# SCART_SWITCH-5CH.net
KiCad netlist of a schematic drawn in EAGLE
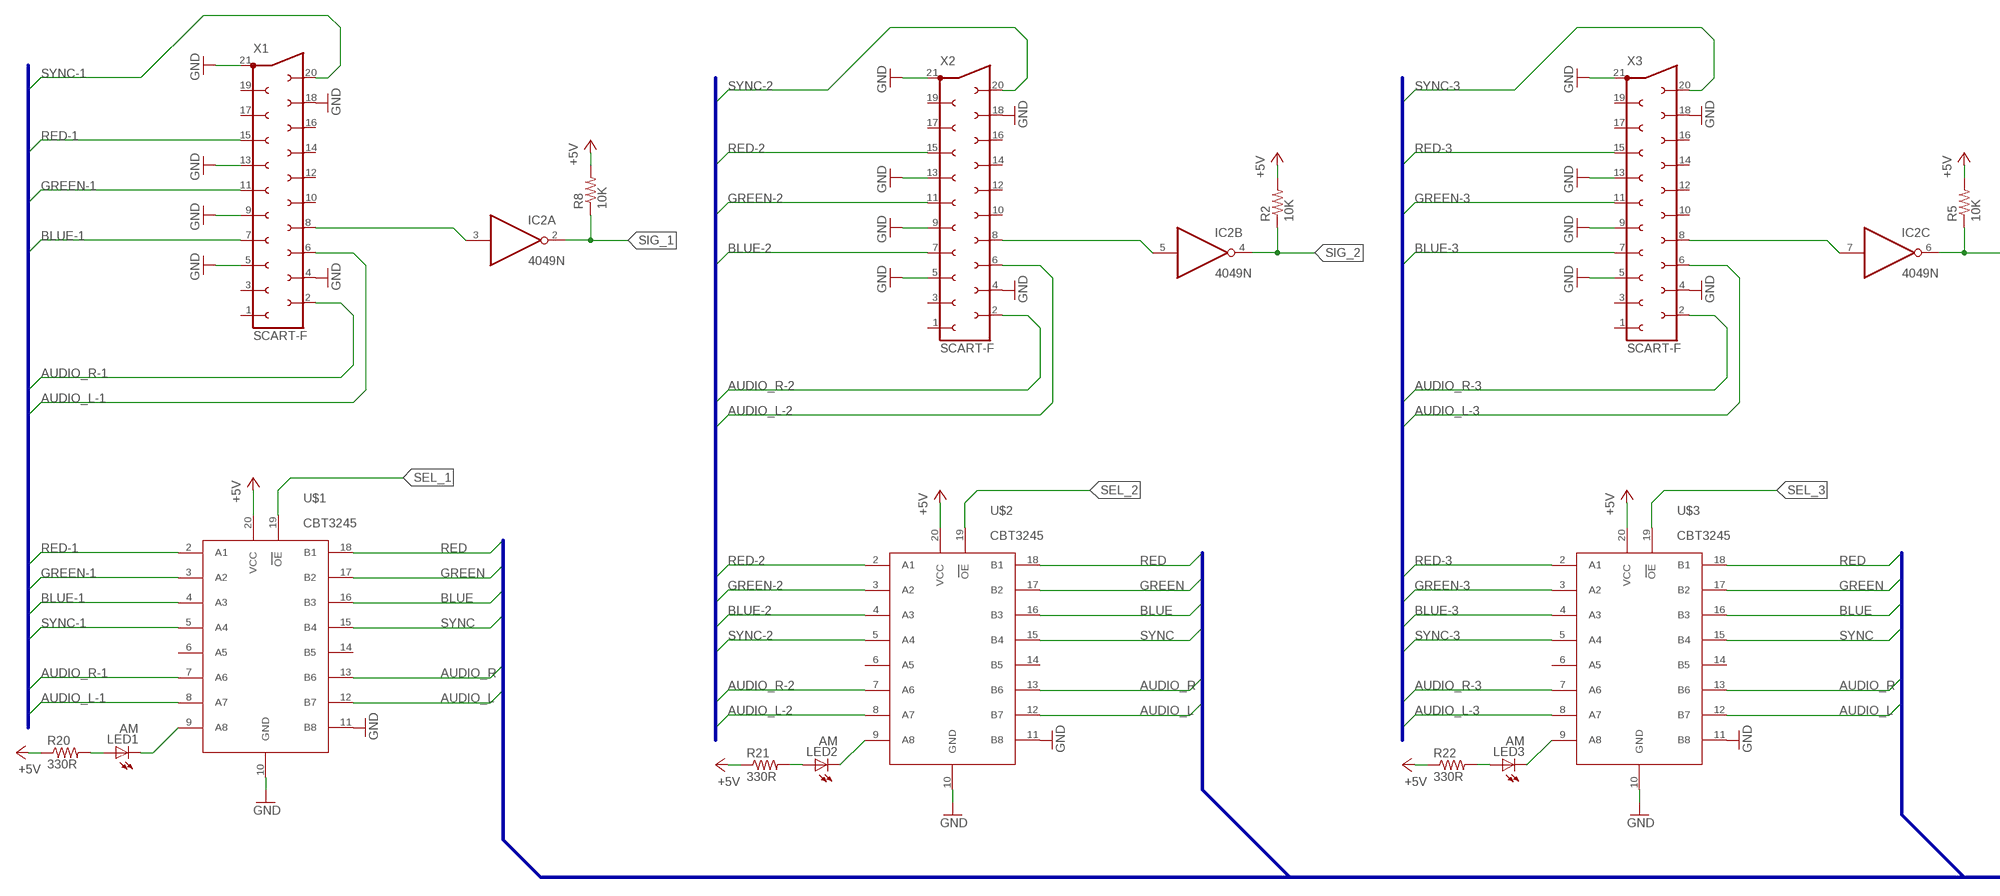
[diagram p0: schematic, sheet 1, part 1 of 2]
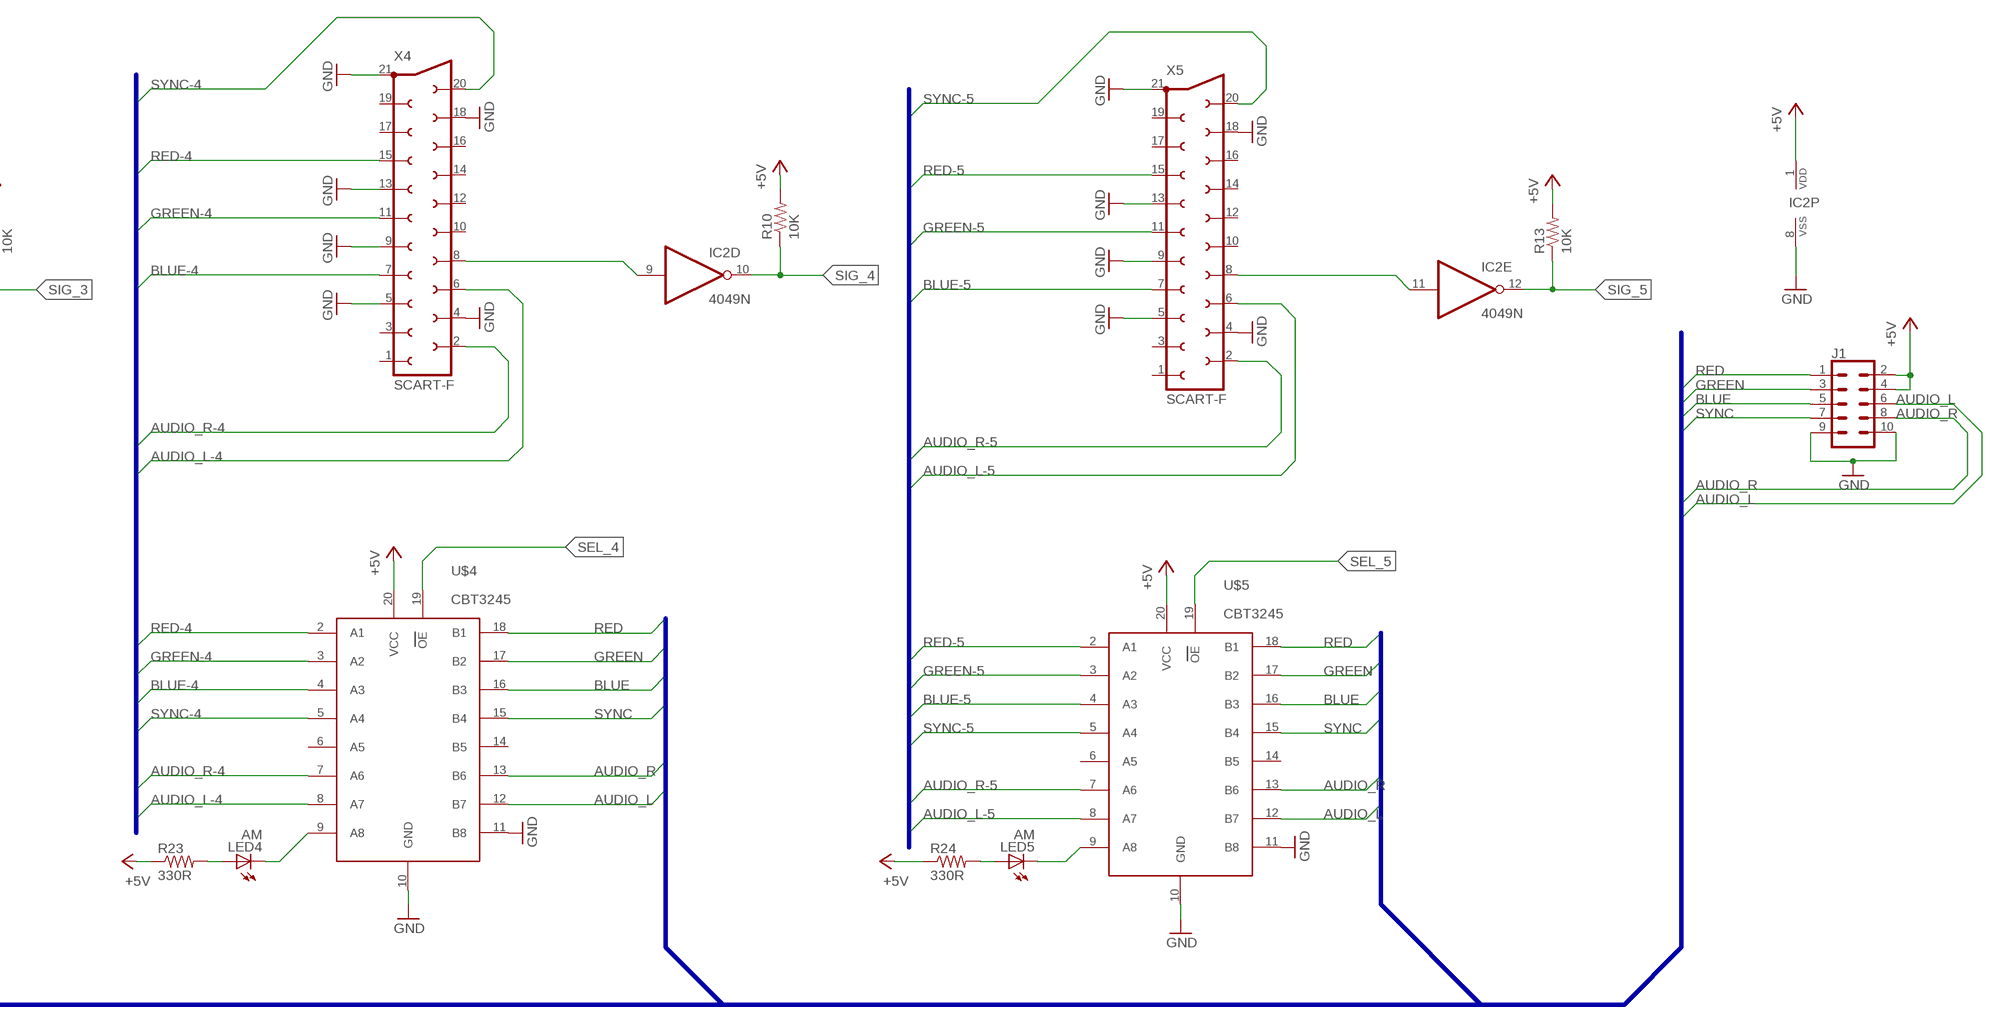
[diagram p1: schematic, sheet 1, part 2 of 2]
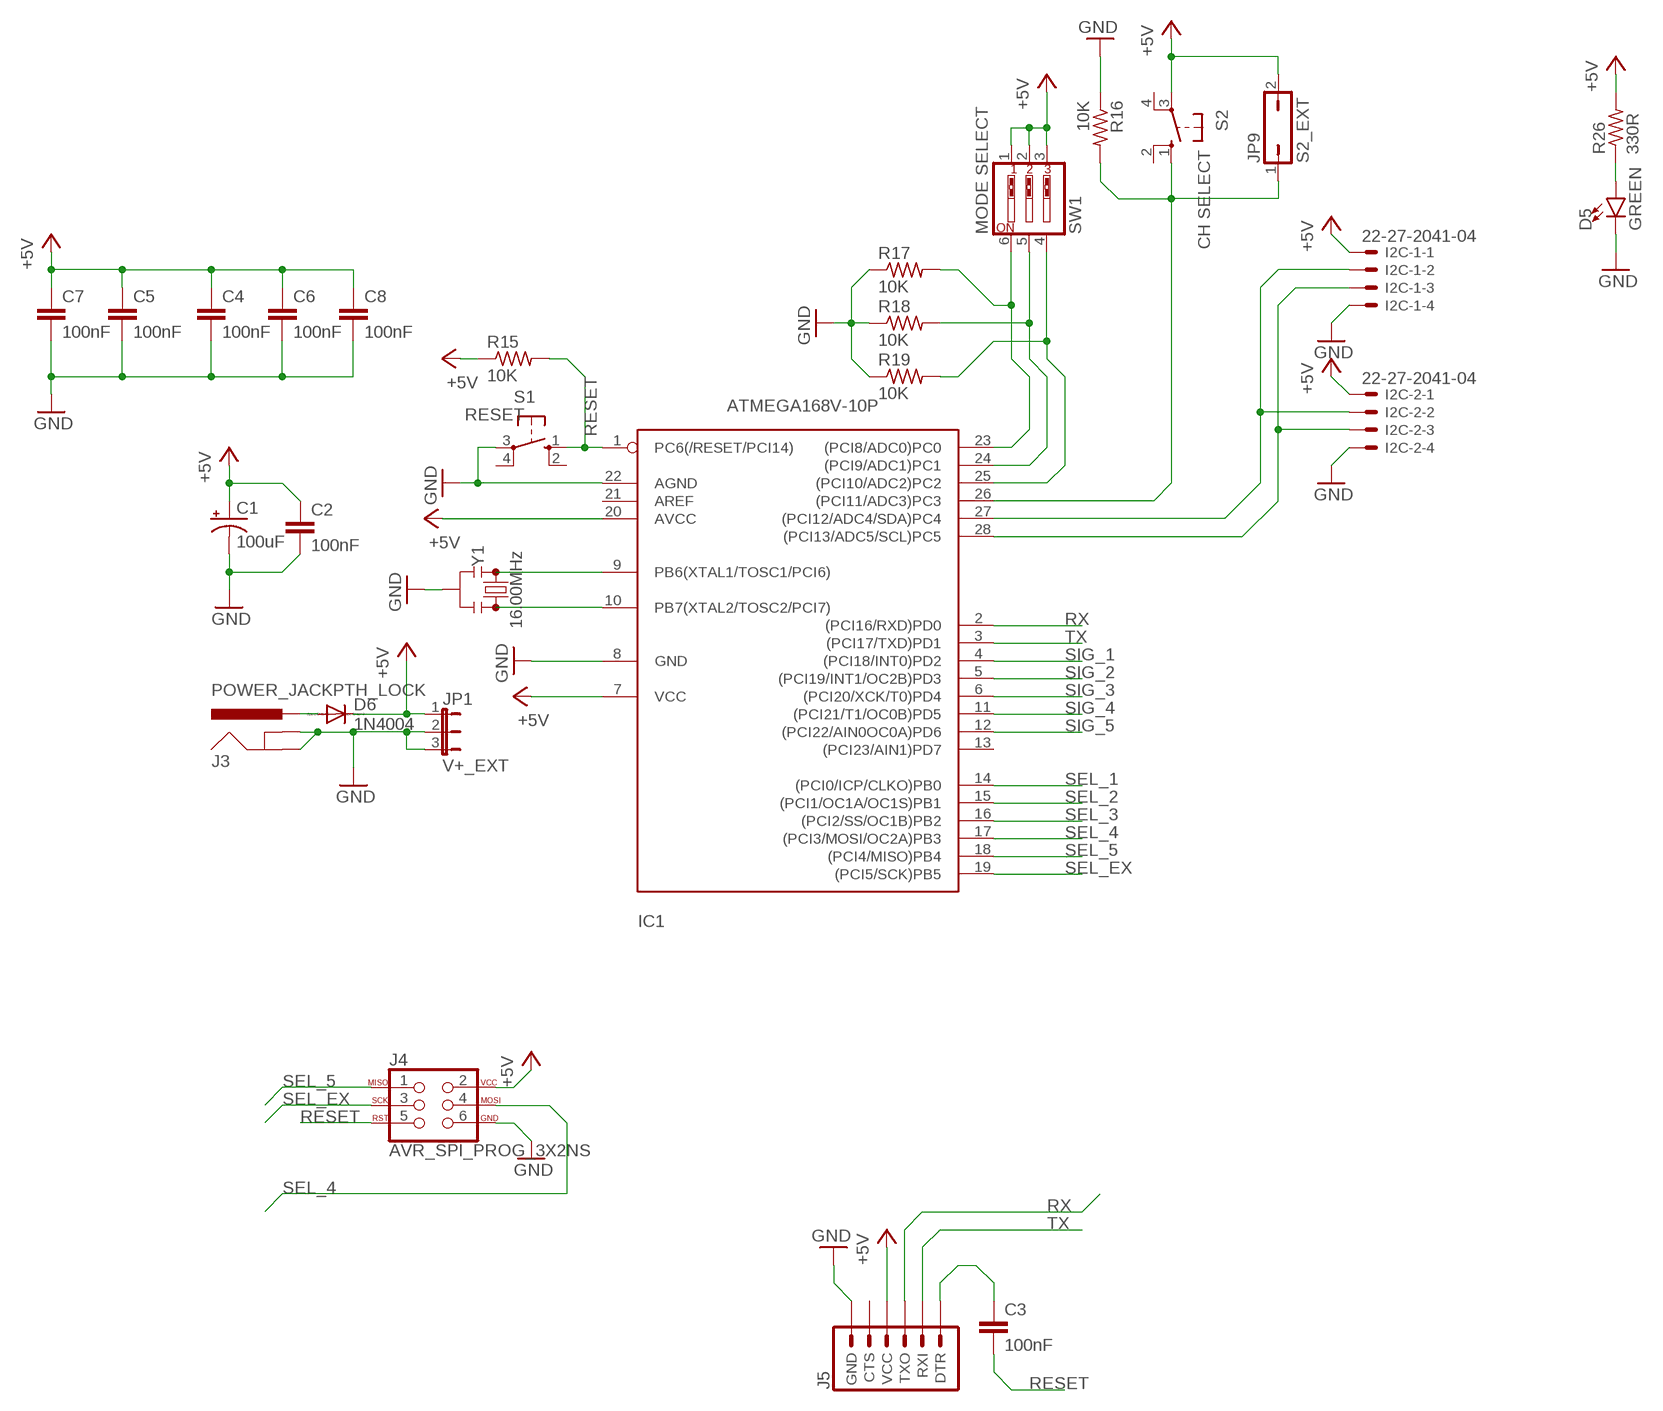
[diagram p2: schematic, sheet 2]

(export (version "E")
  (design (tool "Eeschema 10.0.6"))
  (components
    (comp (ref "IC2")
      (value "4049N")
      (footprint "eagle-import:DIL16")
      (libsource (lib "eagle-import") (part "4049N"))
    )
    (comp (ref "J1")
      (value "CONN_05X2SHD")
      (footprint "eagle-import:2X5-SHROUDED")
      (libsource (lib "eagle-import") (part "CONN_05X2SHD"))
    )
    (comp (ref "LED1")
      (value "AM")
      (footprint "eagle-import:LED5MM")
      (libsource (lib "eagle-import") (part "led_LED5MM"))
    )
    (comp (ref "LED2")
      (value "AM")
      (footprint "eagle-import:LED5MM")
      (libsource (lib "eagle-import") (part "led_LED5MM"))
    )
    (comp (ref "LED3")
      (value "AM")
      (footprint "eagle-import:LED5MM")
      (libsource (lib "eagle-import") (part "led_LED5MM"))
    )
    (comp (ref "LED4")
      (value "AM")
      (footprint "eagle-import:LED5MM")
      (libsource (lib "eagle-import") (part "led_LED5MM"))
    )
    (comp (ref "LED5")
      (value "AM")
      (footprint "eagle-import:LED5MM")
      (libsource (lib "eagle-import") (part "led_LED5MM"))
    )
    (comp (ref "R2")
      (value "10K")
      (footprint "eagle-import:0204_7")
      (libsource (lib "eagle-import") (part "resistor_R-US_0204/7"))
    )
    (comp (ref "R5")
      (value "10K")
      (footprint "eagle-import:0204_7")
      (libsource (lib "eagle-import") (part "resistor_R-US_0204/7"))
    )
    (comp (ref "R8")
      (value "10K")
      (footprint "eagle-import:0204_7")
      (libsource (lib "eagle-import") (part "resistor_R-US_0204/7"))
    )
    (comp (ref "R10")
      (value "10K")
      (footprint "eagle-import:0204_7")
      (libsource (lib "eagle-import") (part "resistor_R-US_0204/7"))
    )
    (comp (ref "R13")
      (value "10K")
      (footprint "eagle-import:0204_7")
      (libsource (lib "eagle-import") (part "resistor_R-US_0204/7"))
    )
    (comp (ref "R20")
      (value "330R")
      (footprint "eagle-import:0207_2V")
      (libsource (lib "eagle-import") (part "R-US_0207/2V"))
    )
    (comp (ref "R21")
      (value "330R")
      (footprint "eagle-import:0207_2V")
      (libsource (lib "eagle-import") (part "R-US_0207/2V"))
    )
    (comp (ref "R22")
      (value "330R")
      (footprint "eagle-import:0207_2V")
      (libsource (lib "eagle-import") (part "R-US_0207/2V"))
    )
    (comp (ref "R23")
      (value "330R")
      (footprint "eagle-import:0207_2V")
      (libsource (lib "eagle-import") (part "R-US_0207/2V"))
    )
    (comp (ref "R24")
      (value "330R")
      (footprint "eagle-import:0207_2V")
      (libsource (lib "eagle-import") (part "R-US_0207/2V"))
    )
    (comp (ref "U$1")
      (value "CBT3245")
      (footprint "eagle-import:SO20")
      (libsource (lib "eagle-import") (part "CBT3245"))
    )
    (comp (ref "U$2")
      (value "CBT3245")
      (footprint "eagle-import:SO20")
      (libsource (lib "eagle-import") (part "CBT3245"))
    )
    (comp (ref "U$3")
      (value "CBT3245")
      (footprint "eagle-import:SO20")
      (libsource (lib "eagle-import") (part "CBT3245"))
    )
    (comp (ref "U$4")
      (value "CBT3245")
      (footprint "eagle-import:SO20")
      (libsource (lib "eagle-import") (part "CBT3245"))
    )
    (comp (ref "U$5")
      (value "CBT3245")
      (footprint "eagle-import:SO20")
      (libsource (lib "eagle-import") (part "CBT3245"))
    )
    (comp (ref "X1")
      (value "SCART-F")
      (footprint "eagle-import:SCART-F")
      (libsource (lib "eagle-import") (part "SCART-F"))
    )
    (comp (ref "X2")
      (value "SCART-F")
      (footprint "eagle-import:SCART-F")
      (libsource (lib "eagle-import") (part "SCART-F"))
    )
    (comp (ref "X3")
      (value "SCART-F")
      (footprint "eagle-import:SCART-F")
      (libsource (lib "eagle-import") (part "SCART-F"))
    )
    (comp (ref "X4")
      (value "SCART-F")
      (footprint "eagle-import:SCART-F")
      (libsource (lib "eagle-import") (part "SCART-F"))
    )
    (comp (ref "X5")
      (value "SCART-F")
      (footprint "eagle-import:SCART-F")
      (libsource (lib "eagle-import") (part "SCART-F"))
    )
    (comp (ref "C1")
      (value "100uF")
      (footprint "eagle-import:E2,5-7")
      (libsource (lib "eagle-import") (part "CPOL-USE2.5-7"))
    )
    (comp (ref "C2")
      (value "100nF")
      (footprint "eagle-import:C075-032X103")
      (libsource (lib "eagle-import") (part "C-EU075-032X103"))
    )
    (comp (ref "C3")
      (value "100nF")
      (footprint "eagle-import:C075-032X103")
      (libsource (lib "eagle-import") (part "C-EU075-032X103"))
    )
    (comp (ref "C4")
      (value "100nF")
      (footprint "eagle-import:C075-032X103")
      (libsource (lib "eagle-import") (part "C-EU075-032X103"))
    )
    (comp (ref "C5")
      (value "100nF")
      (footprint "eagle-import:C075-032X103")
      (libsource (lib "eagle-import") (part "C-EU075-032X103"))
    )
    (comp (ref "C6")
      (value "100nF")
      (footprint "eagle-import:C075-032X103")
      (libsource (lib "eagle-import") (part "C-EU075-032X103"))
    )
    (comp (ref "C7")
      (value "100nF")
      (footprint "eagle-import:C075-032X103")
      (libsource (lib "eagle-import") (part "C-EU075-032X103"))
    )
    (comp (ref "C8")
      (value "100nF")
      (footprint "eagle-import:C075-032X103")
      (libsource (lib "eagle-import") (part "C-EU075-032X103"))
    )
    (comp (ref "D5")
      (value "GREEN")
      (footprint "eagle-import:LED_5MM")
      (libsource (lib "eagle-import") (part "LED5MM"))
    )
    (comp (ref "D6")
      (value "1N4004")
      (footprint "eagle-import:DO41-10")
      (libsource (lib "eagle-import") (part "1N4004"))
    )
    (comp (ref "I2C-1")
      (value "22-27-2041-04")
      (footprint "eagle-import:6410-04")
      (libsource (lib "eagle-import") (part "22-?-0427-2041"))
    )
    (comp (ref "I2C-2")
      (value "22-27-2041-04")
      (footprint "eagle-import:6410-04")
      (libsource (lib "eagle-import") (part "22-?-0427-2041"))
    )
    (comp (ref "IC1")
      (value "ATMEGA168V-10P")
      (footprint "eagle-import:DIL28-3")
      (libsource (lib "eagle-import") (part "ATMEGA168PV-10"))
    )
    (comp (ref "J3")
      (value "POWER_JACKPTH_LOCK")
      (footprint "eagle-import:POWER_JACK_PTH_LOCK")
      (libsource (lib "eagle-import") (part "POWER_JACKPTH_LOCK"))
    )
    (comp (ref "J4")
      (value "AVR_SPI_PROG_3X2NS")
      (footprint "eagle-import:2X3-NS")
      (libsource (lib "eagle-import") (part "AVR_SPI_PROG_3X2NS"))
    )
    (comp (ref "J5")
      (value "6_PIN_SERIAL_TARGETSILK")
      (footprint "eagle-import:6_PIN_SERIAL_TARGET_SIDE_W_SILK")
      (libsource (lib "eagle-import") (part "6_PIN_SERIAL_TARGETSILK"))
    )
    (comp (ref "JP1")
      (value "V+_EXT")
      (footprint "eagle-import:JP2")
      (libsource (lib "eagle-import") (part "JP2E"))
    )
    (comp (ref "JP9")
      (value "S2_EXT")
      (footprint "eagle-import:JP1")
      (libsource (lib "eagle-import") (part "JP1Q"))
    )
    (comp (ref "R15")
      (value "10K")
      (footprint "eagle-import:0204_7")
      (libsource (lib "eagle-import") (part "R-US_0204/7"))
    )
    (comp (ref "R16")
      (value "10K")
      (footprint "eagle-import:0204_7")
      (libsource (lib "eagle-import") (part "R-US_0204/7"))
    )
    (comp (ref "R17")
      (value "10K")
      (footprint "eagle-import:0204_7")
      (libsource (lib "eagle-import") (part "R-US_0204/7"))
    )
    (comp (ref "R18")
      (value "10K")
      (footprint "eagle-import:0204_7")
      (libsource (lib "eagle-import") (part "R-US_0204/7"))
    )
    (comp (ref "R19")
      (value "10K")
      (footprint "eagle-import:0204_7")
      (libsource (lib "eagle-import") (part "R-US_0204/7"))
    )
    (comp (ref "R26")
      (value "330R")
      (footprint "eagle-import:0204_7")
      (libsource (lib "eagle-import") (part "resistor_R-US_0204/7"))
    )
    (comp (ref "S1")
      (value "RESET")
      (footprint "eagle-import:B3F-10XX")
      (fields (field (name "MPN") "B3F-1000"))
      (libsource (lib "eagle-import") (part "10-XX"))
    )
    (comp (ref "S2")
      (value "CH SELECT")
      (footprint "eagle-import:B3F-10XX")
      (fields (field (name "MPN") "B3F-1000"))
      (libsource (lib "eagle-import") (part "10-XX"))
    )
    (comp (ref "SW1")
      (value "MODE SELECT")
      (footprint "eagle-import:EDG-03")
      (libsource (lib "eagle-import") (part "SW_DIP-3"))
    )
    (comp (ref "Y1")
      (value "16.00MHz")
      (footprint "eagle-import:RESONATOR-PTH-7.6X3.8")
      (libsource (lib "eagle-import") (part "RESONATORPTH-7.6X3.8"))
    )
  )
  (nets
    (net (code "2") (name "+5V") (class "Default")
      (node (ref "C1") (pin "+") (pinfunction "+_+") (pintype "passive"))
      (node (ref "C2") (pin "1") (pinfunction "1_1") (pintype "passive"))
      (node (ref "C4") (pin "1") (pinfunction "1_1") (pintype "passive"))
      (node (ref "C5") (pin "1") (pinfunction "1_1") (pintype "passive"))
      (node (ref "C6") (pin "1") (pinfunction "1_1") (pintype "passive"))
      (node (ref "C7") (pin "1") (pinfunction "1_1") (pintype "passive"))
      (node (ref "C8") (pin "1") (pinfunction "1_1") (pintype "passive"))
      (node (ref "D6") (pin "C") (pinfunction "C_C") (pintype "passive"))
      (node (ref "I2C-1") (pin "1") (pinfunction "S_1") (pintype "passive"))
      (node (ref "I2C-2") (pin "1") (pinfunction "S_1") (pintype "passive"))
      (node (ref "IC1") (pin "20") (pinfunction "AVCC_20") (pintype "bidirectional"))
      (node (ref "IC1") (pin "7") (pinfunction "VCC_7") (pintype "bidirectional"))
      (node (ref "IC2") (pin "1") (pinfunction "VDD_1") (pintype "power_in"))
      (node (ref "J1") (pin "2") (pinfunction "2_2") (pintype "passive"))
      (node (ref "J1") (pin "4") (pinfunction "4_4") (pintype "passive"))
      (node (ref "J4") (pin "2") (pinfunction "2_2") (pintype "passive"))
      (node (ref "J5") (pin "P$4") (pinfunction "VCC_P$4") (pintype "passive"))
      (node (ref "JP1") (pin "1") (pinfunction "1_1") (pintype "passive"))
      (node (ref "JP9") (pin "2") (pinfunction "2_2") (pintype "passive"))
      (node (ref "R10") (pin "2") (pinfunction "2_2") (pintype "passive"))
      (node (ref "R13") (pin "2") (pinfunction "2_2") (pintype "passive"))
      (node (ref "R15") (pin "1") (pinfunction "1_1") (pintype "passive"))
      (node (ref "R2") (pin "2") (pinfunction "2_2") (pintype "passive"))
      (node (ref "R20") (pin "1") (pinfunction "1_1") (pintype "passive"))
      (node (ref "R21") (pin "1") (pinfunction "1_1") (pintype "passive"))
      (node (ref "R22") (pin "1") (pinfunction "1_1") (pintype "passive"))
      (node (ref "R23") (pin "1") (pinfunction "1_1") (pintype "passive"))
      (node (ref "R24") (pin "1") (pinfunction "1_1") (pintype "passive"))
      (node (ref "R26") (pin "2") (pinfunction "2_2") (pintype "passive"))
      (node (ref "R5") (pin "2") (pinfunction "2_2") (pintype "passive"))
      (node (ref "R8") (pin "2") (pinfunction "2_2") (pintype "passive"))
      (node (ref "S2") (pin "3") (pinfunction "P_3") (pintype "passive"))
      (node (ref "SW1") (pin "1") (pinfunction "1_1") (pintype "passive"))
      (node (ref "SW1") (pin "2") (pinfunction "2_2") (pintype "passive"))
      (node (ref "SW1") (pin "3") (pinfunction "3_3") (pintype "passive"))
      (node (ref "U$1") (pin "20") (pinfunction "VCC_20") (pintype "bidirectional"))
      (node (ref "U$2") (pin "20") (pinfunction "VCC_20") (pintype "bidirectional"))
      (node (ref "U$3") (pin "20") (pinfunction "VCC_20") (pintype "bidirectional"))
      (node (ref "U$4") (pin "20") (pinfunction "VCC_20") (pintype "bidirectional"))
      (node (ref "U$5") (pin "20") (pinfunction "VCC_20") (pintype "bidirectional"))
    )
    (net (code "4") (name "AUDIO_L") (class "Default")
      (node (ref "J1") (pin "6") (pinfunction "6_6") (pintype "passive"))
      (node (ref "U$1") (pin "12") (pinfunction "B7_12") (pintype "bidirectional"))
      (node (ref "U$2") (pin "12") (pinfunction "B7_12") (pintype "bidirectional"))
      (node (ref "U$3") (pin "12") (pinfunction "B7_12") (pintype "bidirectional"))
      (node (ref "U$4") (pin "12") (pinfunction "B7_12") (pintype "bidirectional"))
      (node (ref "U$5") (pin "12") (pinfunction "B7_12") (pintype "bidirectional"))
    )
    (net (code "5") (name "AUDIO_L-1") (class "Default")
      (node (ref "U$1") (pin "8") (pinfunction "A7_8") (pintype "bidirectional"))
      (node (ref "X1") (pin "6") (pinfunction "6_6") (pintype "passive"))
    )
    (net (code "6") (name "AUDIO_L-2") (class "Default")
      (node (ref "U$2") (pin "8") (pinfunction "A7_8") (pintype "bidirectional"))
      (node (ref "X2") (pin "6") (pinfunction "6_6") (pintype "passive"))
    )
    (net (code "7") (name "AUDIO_L-3") (class "Default")
      (node (ref "U$3") (pin "8") (pinfunction "A7_8") (pintype "bidirectional"))
      (node (ref "X3") (pin "6") (pinfunction "6_6") (pintype "passive"))
    )
    (net (code "8") (name "AUDIO_L-4") (class "Default")
      (node (ref "U$4") (pin "8") (pinfunction "A7_8") (pintype "bidirectional"))
      (node (ref "X4") (pin "6") (pinfunction "6_6") (pintype "passive"))
    )
    (net (code "9") (name "AUDIO_L-5") (class "Default")
      (node (ref "U$5") (pin "8") (pinfunction "A7_8") (pintype "bidirectional"))
      (node (ref "X5") (pin "6") (pinfunction "6_6") (pintype "passive"))
    )
    (net (code "10") (name "AUDIO_R") (class "Default")
      (node (ref "J1") (pin "8") (pinfunction "8_8") (pintype "passive"))
      (node (ref "U$1") (pin "13") (pinfunction "B6_13") (pintype "bidirectional"))
      (node (ref "U$2") (pin "13") (pinfunction "B6_13") (pintype "bidirectional"))
      (node (ref "U$3") (pin "13") (pinfunction "B6_13") (pintype "bidirectional"))
      (node (ref "U$4") (pin "13") (pinfunction "B6_13") (pintype "bidirectional"))
      (node (ref "U$5") (pin "13") (pinfunction "B6_13") (pintype "bidirectional"))
    )
    (net (code "11") (name "AUDIO_R-1") (class "Default")
      (node (ref "U$1") (pin "7") (pinfunction "A6_7") (pintype "bidirectional"))
      (node (ref "X1") (pin "2") (pinfunction "2_2") (pintype "passive"))
    )
    (net (code "12") (name "AUDIO_R-2") (class "Default")
      (node (ref "U$2") (pin "7") (pinfunction "A6_7") (pintype "bidirectional"))
      (node (ref "X2") (pin "2") (pinfunction "2_2") (pintype "passive"))
    )
    (net (code "13") (name "AUDIO_R-3") (class "Default")
      (node (ref "U$3") (pin "7") (pinfunction "A6_7") (pintype "bidirectional"))
      (node (ref "X3") (pin "2") (pinfunction "2_2") (pintype "passive"))
    )
    (net (code "14") (name "AUDIO_R-4") (class "Default")
      (node (ref "U$4") (pin "7") (pinfunction "A6_7") (pintype "bidirectional"))
      (node (ref "X4") (pin "2") (pinfunction "2_2") (pintype "passive"))
    )
    (net (code "15") (name "AUDIO_R-5") (class "Default")
      (node (ref "U$5") (pin "7") (pinfunction "A6_7") (pintype "bidirectional"))
      (node (ref "X5") (pin "2") (pinfunction "2_2") (pintype "passive"))
    )
    (net (code "16") (name "BLUE") (class "Default")
      (node (ref "J1") (pin "5") (pinfunction "5_5") (pintype "passive"))
      (node (ref "U$1") (pin "16") (pinfunction "B3_16") (pintype "bidirectional"))
      (node (ref "U$2") (pin "16") (pinfunction "B3_16") (pintype "bidirectional"))
      (node (ref "U$3") (pin "16") (pinfunction "B3_16") (pintype "bidirectional"))
      (node (ref "U$4") (pin "16") (pinfunction "B3_16") (pintype "bidirectional"))
      (node (ref "U$5") (pin "16") (pinfunction "B3_16") (pintype "bidirectional"))
    )
    (net (code "17") (name "BLUE-1") (class "Default")
      (node (ref "U$1") (pin "4") (pinfunction "A3_4") (pintype "bidirectional"))
      (node (ref "X1") (pin "7") (pinfunction "7_7") (pintype "passive"))
    )
    (net (code "18") (name "BLUE-2") (class "Default")
      (node (ref "U$2") (pin "4") (pinfunction "A3_4") (pintype "bidirectional"))
      (node (ref "X2") (pin "7") (pinfunction "7_7") (pintype "passive"))
    )
    (net (code "19") (name "BLUE-3") (class "Default")
      (node (ref "U$3") (pin "4") (pinfunction "A3_4") (pintype "bidirectional"))
      (node (ref "X3") (pin "7") (pinfunction "7_7") (pintype "passive"))
    )
    (net (code "20") (name "BLUE-4") (class "Default")
      (node (ref "U$4") (pin "4") (pinfunction "A3_4") (pintype "bidirectional"))
      (node (ref "X4") (pin "7") (pinfunction "7_7") (pintype "passive"))
    )
    (net (code "21") (name "BLUE-5") (class "Default")
      (node (ref "U$5") (pin "4") (pinfunction "A3_4") (pintype "bidirectional"))
      (node (ref "X5") (pin "7") (pinfunction "7_7") (pintype "passive"))
    )
    (net (code "22") (name "GND") (class "Default")
      (node (ref "C1") (pin "-") (pinfunction "-_-") (pintype "passive"))
      (node (ref "C2") (pin "2") (pinfunction "2_2") (pintype "passive"))
      (node (ref "C4") (pin "2") (pinfunction "2_2") (pintype "passive"))
      (node (ref "C5") (pin "2") (pinfunction "2_2") (pintype "passive"))
      (node (ref "C6") (pin "2") (pinfunction "2_2") (pintype "passive"))
      (node (ref "C7") (pin "2") (pinfunction "2_2") (pintype "passive"))
      (node (ref "C8") (pin "2") (pinfunction "2_2") (pintype "passive"))
      (node (ref "D5") (pin "K") (pinfunction "C_K") (pintype "passive"))
      (node (ref "I2C-1") (pin "4") (pinfunction "S_4") (pintype "passive"))
      (node (ref "I2C-2") (pin "4") (pinfunction "S_4") (pintype "passive"))
      (node (ref "IC1") (pin "22") (pinfunction "AGND_22") (pintype "bidirectional"))
      (node (ref "IC1") (pin "8") (pinfunction "GND_8") (pintype "bidirectional"))
      (node (ref "IC2") (pin "8") (pinfunction "VSS_8") (pintype "power_in"))
      (node (ref "J1") (pin "10") (pinfunction "10_10") (pintype "passive"))
      (node (ref "J1") (pin "9") (pinfunction "9_9") (pintype "passive"))
      (node (ref "J3") (pin "GND") (pinfunction "GND_GND") (pintype "bidirectional"))
      (node (ref "J3") (pin "GNDBREAK") (pinfunction "GNDBREAK_GNDBREAK") (pintype "bidirectional"))
      (node (ref "J4") (pin "6") (pinfunction "6_6") (pintype "passive"))
      (node (ref "J5") (pin "P$6") (pinfunction "GND_P$6") (pintype "passive"))
      (node (ref "JP1") (pin "2") (pinfunction "2_2") (pintype "passive"))
      (node (ref "JP1") (pin "3") (pinfunction "3_3") (pintype "passive"))
      (node (ref "R16") (pin "1") (pinfunction "1_1") (pintype "passive"))
      (node (ref "R17") (pin "1") (pinfunction "1_1") (pintype "passive"))
      (node (ref "R18") (pin "1") (pinfunction "1_1") (pintype "passive"))
      (node (ref "R19") (pin "1") (pinfunction "1_1") (pintype "passive"))
      (node (ref "S1") (pin "3") (pinfunction "P_3") (pintype "passive"))
      (node (ref "U$1") (pin "10") (pinfunction "GND_10") (pintype "bidirectional"))
      (node (ref "U$1") (pin "11") (pinfunction "B8_11") (pintype "bidirectional"))
      (node (ref "U$2") (pin "10") (pinfunction "GND_10") (pintype "bidirectional"))
      (node (ref "U$2") (pin "11") (pinfunction "B8_11") (pintype "bidirectional"))
      (node (ref "U$3") (pin "10") (pinfunction "GND_10") (pintype "bidirectional"))
      (node (ref "U$3") (pin "11") (pinfunction "B8_11") (pintype "bidirectional"))
      (node (ref "U$4") (pin "10") (pinfunction "GND_10") (pintype "bidirectional"))
      (node (ref "U$4") (pin "11") (pinfunction "B8_11") (pintype "bidirectional"))
      (node (ref "U$5") (pin "10") (pinfunction "GND_10") (pintype "bidirectional"))
      (node (ref "U$5") (pin "11") (pinfunction "B8_11") (pintype "bidirectional"))
      (node (ref "X1") (pin "13") (pinfunction "13_13") (pintype "passive"))
      (node (ref "X1") (pin "18") (pinfunction "18_18") (pintype "passive"))
      (node (ref "X1") (pin "21") (pinfunction "21_21") (pintype "passive"))
      (node (ref "X1") (pin "4") (pinfunction "4_4") (pintype "passive"))
      (node (ref "X1") (pin "5") (pinfunction "5_5") (pintype "passive"))
      (node (ref "X1") (pin "9") (pinfunction "9_9") (pintype "passive"))
      (node (ref "X2") (pin "13") (pinfunction "13_13") (pintype "passive"))
      (node (ref "X2") (pin "18") (pinfunction "18_18") (pintype "passive"))
      (node (ref "X2") (pin "21") (pinfunction "21_21") (pintype "passive"))
      (node (ref "X2") (pin "4") (pinfunction "4_4") (pintype "passive"))
      (node (ref "X2") (pin "5") (pinfunction "5_5") (pintype "passive"))
      (node (ref "X2") (pin "9") (pinfunction "9_9") (pintype "passive"))
      (node (ref "X3") (pin "13") (pinfunction "13_13") (pintype "passive"))
      (node (ref "X3") (pin "18") (pinfunction "18_18") (pintype "passive"))
      (node (ref "X3") (pin "21") (pinfunction "21_21") (pintype "passive"))
      (node (ref "X3") (pin "4") (pinfunction "4_4") (pintype "passive"))
      (node (ref "X3") (pin "5") (pinfunction "5_5") (pintype "passive"))
      (node (ref "X3") (pin "9") (pinfunction "9_9") (pintype "passive"))
      (node (ref "X4") (pin "13") (pinfunction "13_13") (pintype "passive"))
      (node (ref "X4") (pin "18") (pinfunction "18_18") (pintype "passive"))
      (node (ref "X4") (pin "21") (pinfunction "21_21") (pintype "passive"))
      (node (ref "X4") (pin "4") (pinfunction "4_4") (pintype "passive"))
      (node (ref "X4") (pin "5") (pinfunction "5_5") (pintype "passive"))
      (node (ref "X4") (pin "9") (pinfunction "9_9") (pintype "passive"))
      (node (ref "X5") (pin "13") (pinfunction "13_13") (pintype "passive"))
      (node (ref "X5") (pin "18") (pinfunction "18_18") (pintype "passive"))
      (node (ref "X5") (pin "21") (pinfunction "21_21") (pintype "passive"))
      (node (ref "X5") (pin "4") (pinfunction "4_4") (pintype "passive"))
      (node (ref "X5") (pin "5") (pinfunction "5_5") (pintype "passive"))
      (node (ref "X5") (pin "9") (pinfunction "9_9") (pintype "passive"))
      (node (ref "Y1") (pin "2") (pinfunction "2_2") (pintype "passive"))
    )
    (net (code "23") (name "GREEN") (class "Default")
      (node (ref "J1") (pin "3") (pinfunction "3_3") (pintype "passive"))
      (node (ref "U$1") (pin "17") (pinfunction "B2_17") (pintype "bidirectional"))
      (node (ref "U$2") (pin "17") (pinfunction "B2_17") (pintype "bidirectional"))
      (node (ref "U$3") (pin "17") (pinfunction "B2_17") (pintype "bidirectional"))
      (node (ref "U$4") (pin "17") (pinfunction "B2_17") (pintype "bidirectional"))
      (node (ref "U$5") (pin "17") (pinfunction "B2_17") (pintype "bidirectional"))
    )
    (net (code "24") (name "GREEN-1") (class "Default")
      (node (ref "U$1") (pin "3") (pinfunction "A2_3") (pintype "bidirectional"))
      (node (ref "X1") (pin "11") (pinfunction "11_11") (pintype "passive"))
    )
    (net (code "25") (name "GREEN-2") (class "Default")
      (node (ref "U$2") (pin "3") (pinfunction "A2_3") (pintype "bidirectional"))
      (node (ref "X2") (pin "11") (pinfunction "11_11") (pintype "passive"))
    )
    (net (code "26") (name "GREEN-3") (class "Default")
      (node (ref "U$3") (pin "3") (pinfunction "A2_3") (pintype "bidirectional"))
      (node (ref "X3") (pin "11") (pinfunction "11_11") (pintype "passive"))
    )
    (net (code "27") (name "GREEN-4") (class "Default")
      (node (ref "U$4") (pin "3") (pinfunction "A2_3") (pintype "bidirectional"))
      (node (ref "X4") (pin "11") (pinfunction "11_11") (pintype "passive"))
    )
    (net (code "28") (name "GREEN-5") (class "Default")
      (node (ref "U$5") (pin "3") (pinfunction "A2_3") (pintype "bidirectional"))
      (node (ref "X5") (pin "11") (pinfunction "11_11") (pintype "passive"))
    )
    (net (code "29") (name "Net-(D5-PadA)") (class "Default")
      (node (ref "D5") (pin "A") (pinfunction "A_A") (pintype "passive"))
      (node (ref "R26") (pin "1") (pinfunction "1_1") (pintype "passive"))
    )
    (net (code "30") (name "Net-(D6-PadA)") (class "Default")
      (node (ref "D6") (pin "A") (pinfunction "A_A") (pintype "passive"))
      (node (ref "J3") (pin "PWR") (pinfunction "PWR_PWR") (pintype "bidirectional"))
    )
    (net (code "31") (name "Net-(I2C-1B-S)") (class "Default")
      (node (ref "I2C-1") (pin "2") (pinfunction "S_2") (pintype "passive"))
      (node (ref "I2C-2") (pin "2") (pinfunction "S_2") (pintype "passive"))
      (node (ref "IC1") (pin "27") (pinfunction "(PCI12/ADC4/SDA)PC4_27") (pintype "bidirectional"))
    )
    (net (code "32") (name "Net-(I2C-1C-S)") (class "Default")
      (node (ref "I2C-1") (pin "3") (pinfunction "S_3") (pintype "passive"))
      (node (ref "I2C-2") (pin "3") (pinfunction "S_3") (pintype "passive"))
      (node (ref "IC1") (pin "28") (pinfunction "(PCI13/ADC5/SCL)PC5_28") (pintype "bidirectional"))
    )
    (net (code "33") (name "Net-(IC1-(PCI8{slash}ADC0)PC0)") (class "Default")
      (node (ref "IC1") (pin "23") (pinfunction "(PCI8/ADC0)PC0_23") (pintype "bidirectional"))
      (node (ref "R17") (pin "2") (pinfunction "2_2") (pintype "passive"))
      (node (ref "SW1") (pin "6") (pinfunction "6_6") (pintype "passive"))
    )
    (net (code "34") (name "Net-(IC1-(PCI9{slash}ADC1)PC1)") (class "Default")
      (node (ref "IC1") (pin "24") (pinfunction "(PCI9/ADC1)PC1_24") (pintype "bidirectional"))
      (node (ref "R18") (pin "2") (pinfunction "2_2") (pintype "passive"))
      (node (ref "SW1") (pin "5") (pinfunction "5_5") (pintype "passive"))
    )
    (net (code "35") (name "Net-(IC1-(PCI10{slash}ADC2)PC2)") (class "Default")
      (node (ref "IC1") (pin "25") (pinfunction "(PCI10/ADC2)PC2_25") (pintype "bidirectional"))
      (node (ref "R19") (pin "2") (pinfunction "2_2") (pintype "passive"))
      (node (ref "SW1") (pin "4") (pinfunction "4_4") (pintype "passive"))
    )
    (net (code "36") (name "Net-(IC1-(PCI11{slash}ADC3)PC3)") (class "Default")
      (node (ref "IC1") (pin "26") (pinfunction "(PCI11/ADC3)PC3_26") (pintype "bidirectional"))
      (node (ref "JP9") (pin "1") (pinfunction "1_1") (pintype "passive"))
      (node (ref "R16") (pin "2") (pinfunction "2_2") (pintype "passive"))
      (node (ref "S2") (pin "1") (pinfunction "S_1") (pintype "passive"))
    )
    (net (code "37") (name "Net-(IC1-PB6(XTAL1{slash}TOSC1{slash}PCI6))") (class "Default")
      (node (ref "IC1") (pin "9") (pinfunction "PB6(XTAL1/TOSC1/PCI6)_9") (pintype "bidirectional"))
      (node (ref "Y1") (pin "1") (pinfunction "1_1") (pintype "passive"))
    )
    (net (code "38") (name "Net-(IC1-PB7(XTAL2{slash}TOSC2{slash}PCI7))") (class "Default")
      (node (ref "IC1") (pin "10") (pinfunction "PB7(XTAL2/TOSC2/PCI7)_10") (pintype "bidirectional"))
      (node (ref "Y1") (pin "3") (pinfunction "3_3") (pintype "passive"))
    )
    (net (code "39") (name "Net-(IC2A-I)") (class "Default")
      (node (ref "IC2") (pin "3") (pinfunction "I_3") (pintype "input"))
      (node (ref "X1") (pin "8") (pinfunction "8_8") (pintype "passive"))
    )
    (net (code "40") (name "Net-(IC2B-I)") (class "Default")
      (node (ref "IC2") (pin "5") (pinfunction "I_5") (pintype "input"))
      (node (ref "X2") (pin "8") (pinfunction "8_8") (pintype "passive"))
    )
    (net (code "41") (name "Net-(IC2C-I)") (class "Default")
      (node (ref "IC2") (pin "7") (pinfunction "I_7") (pintype "input"))
      (node (ref "X3") (pin "8") (pinfunction "8_8") (pintype "passive"))
    )
    (net (code "42") (name "Net-(IC2D-I)") (class "Default")
      (node (ref "IC2") (pin "9") (pinfunction "I_9") (pintype "input"))
      (node (ref "X4") (pin "8") (pinfunction "8_8") (pintype "passive"))
    )
    (net (code "43") (name "Net-(IC2E-I)") (class "Default")
      (node (ref "IC2") (pin "11") (pinfunction "I_11") (pintype "input"))
      (node (ref "X5") (pin "8") (pinfunction "8_8") (pintype "passive"))
    )
    (net (code "44") (name "Net-(J5-DTR)") (class "Default")
      (node (ref "C3") (pin "1") (pinfunction "1_1") (pintype "passive"))
      (node (ref "J5") (pin "P$1") (pinfunction "DTR_P$1") (pintype "passive"))
    )
    (net (code "45") (name "Net-(LED1-C)") (class "Default")
      (node (ref "LED1") (pin "K") (pinfunction "C_K") (pintype "passive"))
      (node (ref "U$1") (pin "9") (pinfunction "A8_9") (pintype "bidirectional"))
    )
    (net (code "46") (name "Net-(LED1-PadA)") (class "Default")
      (node (ref "LED1") (pin "A") (pinfunction "A_A") (pintype "passive"))
      (node (ref "R20") (pin "2") (pinfunction "2_2") (pintype "passive"))
    )
    (net (code "47") (name "Net-(LED2-C)") (class "Default")
      (node (ref "LED2") (pin "K") (pinfunction "C_K") (pintype "passive"))
      (node (ref "U$2") (pin "9") (pinfunction "A8_9") (pintype "bidirectional"))
    )
    (net (code "48") (name "Net-(LED2-PadA)") (class "Default")
      (node (ref "LED2") (pin "A") (pinfunction "A_A") (pintype "passive"))
      (node (ref "R21") (pin "2") (pinfunction "2_2") (pintype "passive"))
    )
    (net (code "49") (name "Net-(LED3-C)") (class "Default")
      (node (ref "LED3") (pin "K") (pinfunction "C_K") (pintype "passive"))
      (node (ref "U$3") (pin "9") (pinfunction "A8_9") (pintype "bidirectional"))
    )
    (net (code "50") (name "Net-(LED3-PadA)") (class "Default")
      (node (ref "LED3") (pin "A") (pinfunction "A_A") (pintype "passive"))
      (node (ref "R22") (pin "2") (pinfunction "2_2") (pintype "passive"))
    )
    (net (code "51") (name "Net-(LED4-C)") (class "Default")
      (node (ref "LED4") (pin "K") (pinfunction "C_K") (pintype "passive"))
      (node (ref "U$4") (pin "9") (pinfunction "A8_9") (pintype "bidirectional"))
    )
    (net (code "52") (name "Net-(LED4-PadA)") (class "Default")
      (node (ref "LED4") (pin "A") (pinfunction "A_A") (pintype "passive"))
      (node (ref "R23") (pin "2") (pinfunction "2_2") (pintype "passive"))
    )
    (net (code "53") (name "Net-(LED5-C)") (class "Default")
      (node (ref "LED5") (pin "K") (pinfunction "C_K") (pintype "passive"))
      (node (ref "U$5") (pin "9") (pinfunction "A8_9") (pintype "bidirectional"))
    )
    (net (code "54") (name "Net-(LED5-PadA)") (class "Default")
      (node (ref "LED5") (pin "A") (pinfunction "A_A") (pintype "passive"))
      (node (ref "R24") (pin "2") (pinfunction "2_2") (pintype "passive"))
    )
    (net (code "55") (name "RED") (class "Default")
      (node (ref "J1") (pin "1") (pinfunction "1_1") (pintype "passive"))
      (node (ref "U$1") (pin "18") (pinfunction "B1_18") (pintype "bidirectional"))
      (node (ref "U$2") (pin "18") (pinfunction "B1_18") (pintype "bidirectional"))
      (node (ref "U$3") (pin "18") (pinfunction "B1_18") (pintype "bidirectional"))
      (node (ref "U$4") (pin "18") (pinfunction "B1_18") (pintype "bidirectional"))
      (node (ref "U$5") (pin "18") (pinfunction "B1_18") (pintype "bidirectional"))
    )
    (net (code "56") (name "RED-1") (class "Default")
      (node (ref "U$1") (pin "2") (pinfunction "A1_2") (pintype "bidirectional"))
      (node (ref "X1") (pin "15") (pinfunction "15_15") (pintype "passive"))
    )
    (net (code "57") (name "RED-2") (class "Default")
      (node (ref "U$2") (pin "2") (pinfunction "A1_2") (pintype "bidirectional"))
      (node (ref "X2") (pin "15") (pinfunction "15_15") (pintype "passive"))
    )
    (net (code "58") (name "RED-3") (class "Default")
      (node (ref "U$3") (pin "2") (pinfunction "A1_2") (pintype "bidirectional"))
      (node (ref "X3") (pin "15") (pinfunction "15_15") (pintype "passive"))
    )
    (net (code "59") (name "RED-4") (class "Default")
      (node (ref "U$4") (pin "2") (pinfunction "A1_2") (pintype "bidirectional"))
      (node (ref "X4") (pin "15") (pinfunction "15_15") (pintype "passive"))
    )
    (net (code "60") (name "RED-5") (class "Default")
      (node (ref "U$5") (pin "2") (pinfunction "A1_2") (pintype "bidirectional"))
      (node (ref "X5") (pin "15") (pinfunction "15_15") (pintype "passive"))
    )
    (net (code "61") (name "RESET") (class "Default")
      (node (ref "C3") (pin "2") (pinfunction "2_2") (pintype "passive"))
      (node (ref "IC1") (pin "1") (pinfunction "PC6(/RESET/PCI14)_1") (pintype "bidirectional"))
      (node (ref "J4") (pin "5") (pinfunction "5_5") (pintype "passive"))
      (node (ref "R15") (pin "2") (pinfunction "2_2") (pintype "passive"))
      (node (ref "S1") (pin "1") (pinfunction "S_1") (pintype "passive"))
    )
    (net (code "62") (name "RX") (class "Default")
      (node (ref "IC1") (pin "2") (pinfunction "(PCI16/RXD)PD0_2") (pintype "bidirectional"))
      (node (ref "J5") (pin "P$2") (pinfunction "TXO_P$2") (pintype "passive"))
    )
    (net (code "63") (name "SEL_1") (class "Default")
      (node (ref "IC1") (pin "14") (pinfunction "(PCI0/ICP/CLKO)PB0_14") (pintype "bidirectional"))
      (node (ref "U$1") (pin "19") (pinfunction "OE_19") (pintype "bidirectional"))
    )
    (net (code "64") (name "SEL_2") (class "Default")
      (node (ref "IC1") (pin "15") (pinfunction "(PCI1/OC1A/OC1S)PB1_15") (pintype "bidirectional"))
      (node (ref "U$2") (pin "19") (pinfunction "OE_19") (pintype "bidirectional"))
    )
    (net (code "65") (name "SEL_3") (class "Default")
      (node (ref "IC1") (pin "16") (pinfunction "(PCI2/SS/OC1B)PB2_16") (pintype "bidirectional"))
      (node (ref "U$3") (pin "19") (pinfunction "OE_19") (pintype "bidirectional"))
    )
    (net (code "66") (name "SEL_4") (class "Default")
      (node (ref "IC1") (pin "17") (pinfunction "(PCI3/MOSI/OC2A)PB3_17") (pintype "bidirectional"))
      (node (ref "J4") (pin "4") (pinfunction "4_4") (pintype "passive"))
      (node (ref "U$4") (pin "19") (pinfunction "OE_19") (pintype "bidirectional"))
    )
    (net (code "67") (name "SEL_5") (class "Default")
      (node (ref "IC1") (pin "18") (pinfunction "(PCI4/MISO)PB4_18") (pintype "bidirectional"))
      (node (ref "J4") (pin "1") (pinfunction "1_1") (pintype "passive"))
      (node (ref "U$5") (pin "19") (pinfunction "OE_19") (pintype "bidirectional"))
    )
    (net (code "68") (name "SEL_EX") (class "Default")
      (node (ref "IC1") (pin "19") (pinfunction "(PCI5/SCK)PB5_19") (pintype "bidirectional"))
      (node (ref "J4") (pin "3") (pinfunction "3_3") (pintype "passive"))
    )
    (net (code "69") (name "SIG_1") (class "Default")
      (node (ref "IC1") (pin "4") (pinfunction "(PCI18/INT0)PD2_4") (pintype "bidirectional"))
      (node (ref "IC2") (pin "2") (pinfunction "O_2") (pintype "output"))
      (node (ref "R8") (pin "1") (pinfunction "1_1") (pintype "passive"))
    )
    (net (code "70") (name "SIG_2") (class "Default")
      (node (ref "IC1") (pin "5") (pinfunction "(PCI19/INT1/OC2B)PD3_5") (pintype "bidirectional"))
      (node (ref "IC2") (pin "4") (pinfunction "O_4") (pintype "output"))
      (node (ref "R2") (pin "1") (pinfunction "1_1") (pintype "passive"))
    )
    (net (code "71") (name "SIG_3") (class "Default")
      (node (ref "IC1") (pin "6") (pinfunction "(PCI20/XCK/T0)PD4_6") (pintype "bidirectional"))
      (node (ref "IC2") (pin "6") (pinfunction "O_6") (pintype "output"))
      (node (ref "R5") (pin "1") (pinfunction "1_1") (pintype "passive"))
    )
    (net (code "72") (name "SIG_4") (class "Default")
      (node (ref "IC1") (pin "11") (pinfunction "(PCI21/T1/OC0B)PD5_11") (pintype "bidirectional"))
      (node (ref "IC2") (pin "10") (pinfunction "O_10") (pintype "output"))
      (node (ref "R10") (pin "1") (pinfunction "1_1") (pintype "passive"))
    )
    (net (code "73") (name "SIG_5") (class "Default")
      (node (ref "IC1") (pin "12") (pinfunction "(PCI22/AIN0OC0A)PD6_12") (pintype "bidirectional"))
      (node (ref "IC2") (pin "12") (pinfunction "O_12") (pintype "output"))
      (node (ref "R13") (pin "1") (pinfunction "1_1") (pintype "passive"))
    )
    (net (code "74") (name "SYNC") (class "Default")
      (node (ref "J1") (pin "7") (pinfunction "7_7") (pintype "passive"))
      (node (ref "U$1") (pin "15") (pinfunction "B4_15") (pintype "bidirectional"))
      (node (ref "U$2") (pin "15") (pinfunction "B4_15") (pintype "bidirectional"))
      (node (ref "U$3") (pin "15") (pinfunction "B4_15") (pintype "bidirectional"))
      (node (ref "U$4") (pin "15") (pinfunction "B4_15") (pintype "bidirectional"))
      (node (ref "U$5") (pin "15") (pinfunction "B4_15") (pintype "bidirectional"))
    )
    (net (code "75") (name "SYNC-1") (class "Default")
      (node (ref "U$1") (pin "5") (pinfunction "A4_5") (pintype "bidirectional"))
      (node (ref "X1") (pin "20") (pinfunction "20_20") (pintype "passive"))
    )
    (net (code "76") (name "SYNC-2") (class "Default")
      (node (ref "U$2") (pin "5") (pinfunction "A4_5") (pintype "bidirectional"))
      (node (ref "X2") (pin "20") (pinfunction "20_20") (pintype "passive"))
    )
    (net (code "77") (name "SYNC-3") (class "Default")
      (node (ref "U$3") (pin "5") (pinfunction "A4_5") (pintype "bidirectional"))
      (node (ref "X3") (pin "20") (pinfunction "20_20") (pintype "passive"))
    )
    (net (code "78") (name "SYNC-4") (class "Default")
      (node (ref "U$4") (pin "5") (pinfunction "A4_5") (pintype "bidirectional"))
      (node (ref "X4") (pin "20") (pinfunction "20_20") (pintype "passive"))
    )
    (net (code "79") (name "SYNC-5") (class "Default")
      (node (ref "U$5") (pin "5") (pinfunction "A4_5") (pintype "bidirectional"))
      (node (ref "X5") (pin "20") (pinfunction "20_20") (pintype "passive"))
    )
    (net (code "80") (name "TX") (class "Default")
      (node (ref "IC1") (pin "3") (pinfunction "(PCI17/TXD)PD1_3") (pintype "bidirectional"))
      (node (ref "J5") (pin "P$3") (pinfunction "RXI_P$3") (pintype "passive"))
    )
    (net (code "81") (name "unconnected-(IC1-(PCI23{slash}AIN1)PD7-Pad13)") (class "Default")
      (node (ref "IC1") (pin "13") (pinfunction "(PCI23/AIN1)PD7_13") (pintype "bidirectional"))
    )
    (net (code "82") (name "unconnected-(IC1-AREF-Pad21)") (class "Default")
      (node (ref "IC1") (pin "21") (pinfunction "AREF_21") (pintype "bidirectional"))
    )
    (net (code "83") (name "unconnected-(J5-CTS-PadP$5)") (class "Default")
      (node (ref "J5") (pin "P$5") (pinfunction "CTS_P$5") (pintype "passive"))
    )
    (net (code "84") (name "unconnected-(S1-P1-Pad4)") (class "Default")
      (node (ref "S1") (pin "4") (pinfunction "P1_4") (pintype "passive"))
    )
    (net (code "85") (name "unconnected-(S1-S1-Pad2)") (class "Default")
      (node (ref "S1") (pin "2") (pinfunction "S1_2") (pintype "passive"))
    )
    (net (code "86") (name "unconnected-(S2-P1-Pad4)") (class "Default")
      (node (ref "S2") (pin "4") (pinfunction "P1_4") (pintype "passive"))
    )
    (net (code "87") (name "unconnected-(S2-S1-Pad2)") (class "Default")
      (node (ref "S2") (pin "2") (pinfunction "S1_2") (pintype "passive"))
    )
    (net (code "88") (name "unconnected-(U$1-A5-Pad6)") (class "Default")
      (node (ref "U$1") (pin "6") (pinfunction "A5_6") (pintype "bidirectional"))
    )
    (net (code "89") (name "unconnected-(U$1-B5-Pad14)") (class "Default")
      (node (ref "U$1") (pin "14") (pinfunction "B5_14") (pintype "bidirectional"))
    )
    (net (code "90") (name "unconnected-(U$2-A5-Pad6)") (class "Default")
      (node (ref "U$2") (pin "6") (pinfunction "A5_6") (pintype "bidirectional"))
    )
    (net (code "91") (name "unconnected-(U$2-B5-Pad14)") (class "Default")
      (node (ref "U$2") (pin "14") (pinfunction "B5_14") (pintype "bidirectional"))
    )
    (net (code "92") (name "unconnected-(U$3-A5-Pad6)") (class "Default")
      (node (ref "U$3") (pin "6") (pinfunction "A5_6") (pintype "bidirectional"))
    )
    (net (code "93") (name "unconnected-(U$3-B5-Pad14)") (class "Default")
      (node (ref "U$3") (pin "14") (pinfunction "B5_14") (pintype "bidirectional"))
    )
    (net (code "94") (name "unconnected-(U$4-A5-Pad6)") (class "Default")
      (node (ref "U$4") (pin "6") (pinfunction "A5_6") (pintype "bidirectional"))
    )
    (net (code "95") (name "unconnected-(U$4-B5-Pad14)") (class "Default")
      (node (ref "U$4") (pin "14") (pinfunction "B5_14") (pintype "bidirectional"))
    )
    (net (code "96") (name "unconnected-(U$5-A5-Pad6)") (class "Default")
      (node (ref "U$5") (pin "6") (pinfunction "A5_6") (pintype "bidirectional"))
    )
    (net (code "97") (name "unconnected-(U$5-B5-Pad14)") (class "Default")
      (node (ref "U$5") (pin "14") (pinfunction "B5_14") (pintype "bidirectional"))
    )
    (net (code "98") (name "unconnected-(X1-Pad1)") (class "Default")
      (node (ref "X1") (pin "1") (pinfunction "1_1") (pintype "passive"))
    )
    (net (code "99") (name "unconnected-(X1-Pad3)") (class "Default")
      (node (ref "X1") (pin "3") (pinfunction "3_3") (pintype "passive"))
    )
    (net (code "100") (name "unconnected-(X1-Pad10)") (class "Default")
      (node (ref "X1") (pin "10") (pinfunction "10_10") (pintype "passive"))
    )
    (net (code "101") (name "unconnected-(X1-Pad12)") (class "Default")
      (node (ref "X1") (pin "12") (pinfunction "12_12") (pintype "passive"))
    )
    (net (code "102") (name "unconnected-(X1-Pad14)") (class "Default")
      (node (ref "X1") (pin "14") (pinfunction "14_14") (pintype "passive"))
    )
    (net (code "103") (name "unconnected-(X1-Pad16)") (class "Default")
      (node (ref "X1") (pin "16") (pinfunction "16_16") (pintype "passive"))
    )
    (net (code "104") (name "unconnected-(X1-Pad17)") (class "Default")
      (node (ref "X1") (pin "17") (pinfunction "17_17") (pintype "passive"))
    )
    (net (code "105") (name "unconnected-(X1-Pad19)") (class "Default")
      (node (ref "X1") (pin "19") (pinfunction "19_19") (pintype "passive"))
    )
    (net (code "106") (name "unconnected-(X2-Pad1)") (class "Default")
      (node (ref "X2") (pin "1") (pinfunction "1_1") (pintype "passive"))
    )
    (net (code "107") (name "unconnected-(X2-Pad3)") (class "Default")
      (node (ref "X2") (pin "3") (pinfunction "3_3") (pintype "passive"))
    )
    (net (code "108") (name "unconnected-(X2-Pad10)") (class "Default")
      (node (ref "X2") (pin "10") (pinfunction "10_10") (pintype "passive"))
    )
    (net (code "109") (name "unconnected-(X2-Pad12)") (class "Default")
      (node (ref "X2") (pin "12") (pinfunction "12_12") (pintype "passive"))
    )
    (net (code "110") (name "unconnected-(X2-Pad14)") (class "Default")
      (node (ref "X2") (pin "14") (pinfunction "14_14") (pintype "passive"))
    )
    (net (code "111") (name "unconnected-(X2-Pad16)") (class "Default")
      (node (ref "X2") (pin "16") (pinfunction "16_16") (pintype "passive"))
    )
    (net (code "112") (name "unconnected-(X2-Pad17)") (class "Default")
      (node (ref "X2") (pin "17") (pinfunction "17_17") (pintype "passive"))
    )
    (net (code "113") (name "unconnected-(X2-Pad19)") (class "Default")
      (node (ref "X2") (pin "19") (pinfunction "19_19") (pintype "passive"))
    )
    (net (code "114") (name "unconnected-(X3-Pad1)") (class "Default")
      (node (ref "X3") (pin "1") (pinfunction "1_1") (pintype "passive"))
    )
    (net (code "115") (name "unconnected-(X3-Pad3)") (class "Default")
      (node (ref "X3") (pin "3") (pinfunction "3_3") (pintype "passive"))
    )
    (net (code "116") (name "unconnected-(X3-Pad10)") (class "Default")
      (node (ref "X3") (pin "10") (pinfunction "10_10") (pintype "passive"))
    )
    (net (code "117") (name "unconnected-(X3-Pad12)") (class "Default")
      (node (ref "X3") (pin "12") (pinfunction "12_12") (pintype "passive"))
    )
    (net (code "118") (name "unconnected-(X3-Pad14)") (class "Default")
      (node (ref "X3") (pin "14") (pinfunction "14_14") (pintype "passive"))
    )
    (net (code "119") (name "unconnected-(X3-Pad16)") (class "Default")
      (node (ref "X3") (pin "16") (pinfunction "16_16") (pintype "passive"))
    )
    (net (code "120") (name "unconnected-(X3-Pad17)") (class "Default")
      (node (ref "X3") (pin "17") (pinfunction "17_17") (pintype "passive"))
    )
    (net (code "121") (name "unconnected-(X3-Pad19)") (class "Default")
      (node (ref "X3") (pin "19") (pinfunction "19_19") (pintype "passive"))
    )
    (net (code "122") (name "unconnected-(X4-Pad1)") (class "Default")
      (node (ref "X4") (pin "1") (pinfunction "1_1") (pintype "passive"))
    )
    (net (code "123") (name "unconnected-(X4-Pad3)") (class "Default")
      (node (ref "X4") (pin "3") (pinfunction "3_3") (pintype "passive"))
    )
    (net (code "124") (name "unconnected-(X4-Pad10)") (class "Default")
      (node (ref "X4") (pin "10") (pinfunction "10_10") (pintype "passive"))
    )
    (net (code "125") (name "unconnected-(X4-Pad12)") (class "Default")
      (node (ref "X4") (pin "12") (pinfunction "12_12") (pintype "passive"))
    )
    (net (code "126") (name "unconnected-(X4-Pad14)") (class "Default")
      (node (ref "X4") (pin "14") (pinfunction "14_14") (pintype "passive"))
    )
    (net (code "127") (name "unconnected-(X4-Pad16)") (class "Default")
      (node (ref "X4") (pin "16") (pinfunction "16_16") (pintype "passive"))
    )
    (net (code "128") (name "unconnected-(X4-Pad17)") (class "Default")
      (node (ref "X4") (pin "17") (pinfunction "17_17") (pintype "passive"))
    )
    (net (code "129") (name "unconnected-(X4-Pad19)") (class "Default")
      (node (ref "X4") (pin "19") (pinfunction "19_19") (pintype "passive"))
    )
    (net (code "130") (name "unconnected-(X5-Pad1)") (class "Default")
      (node (ref "X5") (pin "1") (pinfunction "1_1") (pintype "passive"))
    )
    (net (code "131") (name "unconnected-(X5-Pad3)") (class "Default")
      (node (ref "X5") (pin "3") (pinfunction "3_3") (pintype "passive"))
    )
    (net (code "132") (name "unconnected-(X5-Pad10)") (class "Default")
      (node (ref "X5") (pin "10") (pinfunction "10_10") (pintype "passive"))
    )
    (net (code "133") (name "unconnected-(X5-Pad12)") (class "Default")
      (node (ref "X5") (pin "12") (pinfunction "12_12") (pintype "passive"))
    )
    (net (code "134") (name "unconnected-(X5-Pad14)") (class "Default")
      (node (ref "X5") (pin "14") (pinfunction "14_14") (pintype "passive"))
    )
    (net (code "135") (name "unconnected-(X5-Pad16)") (class "Default")
      (node (ref "X5") (pin "16") (pinfunction "16_16") (pintype "passive"))
    )
    (net (code "136") (name "unconnected-(X5-Pad17)") (class "Default")
      (node (ref "X5") (pin "17") (pinfunction "17_17") (pintype "passive"))
    )
    (net (code "137") (name "unconnected-(X5-Pad19)") (class "Default")
      (node (ref "X5") (pin "19") (pinfunction "19_19") (pintype "passive"))
    )
  )
)
